# IMU.net
KiCad netlist of a schematic drawn in Altium Designer
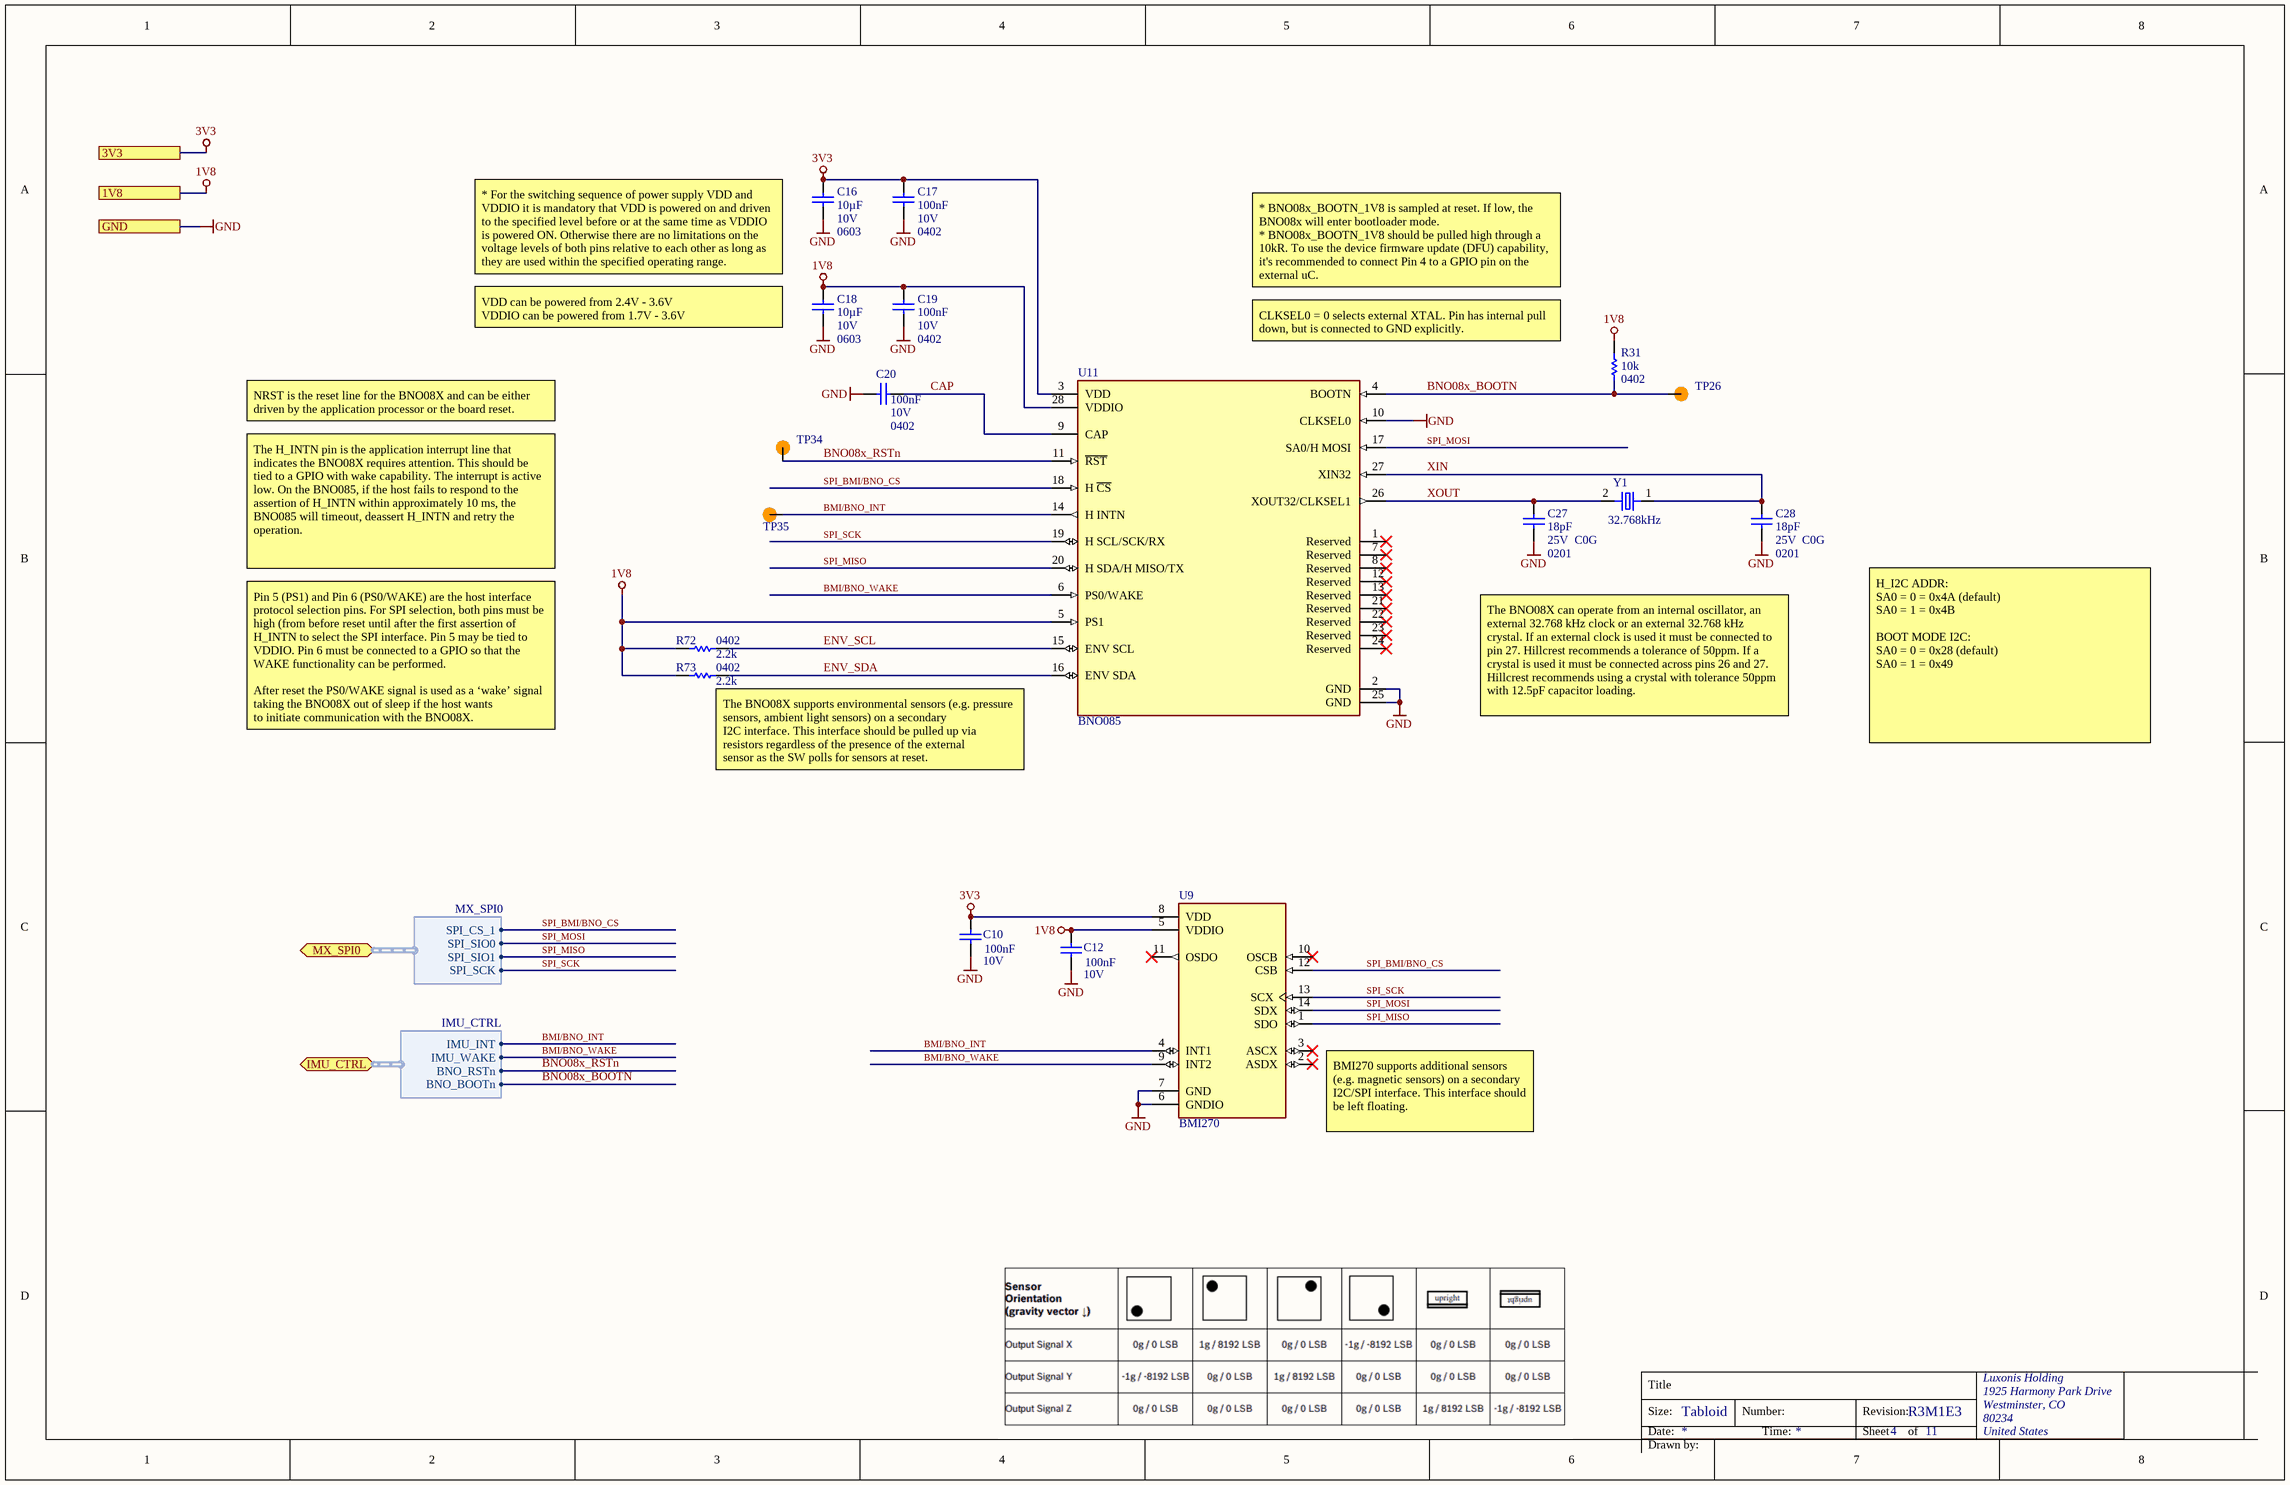
[diagram p0: IMU.SchDoc]

(export (version "E")
  (design (tool "Eeschema 10.0.6"))
  (components
    (comp (ref "C10")
      (value "100nF")
      (footprint "CAPC0402(1005)70_L")
      (description "CAP CER 0.1UF 10V X7R 0402 5%")
      (fields
        (field (name "TOLERANCE") "5%")
        (field (name "VOLTAGE RATING") "10V")
        (field (name "Comment") "GRM155R71A104JA01D")
      )
      (libsource (lib "Luxonis LLC") (part "GRM188R61C475KAAJD"))
    )
    (comp (ref "C12")
      (value "100nF")
      (footprint "CAPC0402(1005)70_L")
      (description "CAP CER 0.1UF 10V X7R 0402 5%")
      (fields
        (field (name "TOLERANCE") "5%")
        (field (name "VOLTAGE RATING") "10V")
        (field (name "Comment") "GRM155R71A104JA01D")
      )
      (libsource (lib "Luxonis LLC") (part "GRM188R61C475KAAJD"))
    )
    (comp (ref "C16")
      (value "10µF")
      (footprint "CAPC0603(1608)100_L")
      (description "CAP CER 10UF 10V X5R 0603 20%")
      (fields
        (field (name "CASE/PACKAGE") "0603")
        (field (name "TOLERANCE") "20%")
        (field (name "VOLTAGE RATING") "10V")
        (field (name "Comment") "GRM188R61A106ME69D")
      )
      (libsource (lib "Luxonis LLC") (part "LLL153C70G474ME17E"))
    )
    (comp (ref "C17")
      (value "100nF")
      (footprint "CAPC0402(1005)70_N")
      (description "CAP CER 0.1UF 10V X7R 0402 5%")
      (fields
        (field (name "CASE/PACKAGE") "0402")
        (field (name "TOLERANCE") "5%")
        (field (name "VOLTAGE RATING") "10V")
        (field (name "Comment") "GRM155R71A104JA01D")
      )
      (libsource (lib "Luxonis LLC") (part "GRM188R61C475KAAJD"))
    )
    (comp (ref "C18")
      (value "10µF")
      (footprint "CAPC0603(1608)100_L")
      (description "CAP CER 10UF 10V X5R 0603 20%")
      (fields
        (field (name "CASE/PACKAGE") "0603")
        (field (name "TOLERANCE") "20%")
        (field (name "VOLTAGE RATING") "10V")
        (field (name "Comment") "GRM188R61A106ME69D")
      )
      (libsource (lib "Luxonis LLC") (part "LLL153C70G474ME17E"))
    )
    (comp (ref "C19")
      (value "100nF")
      (footprint "CAPC0402(1005)70_N")
      (description "CAP CER 0.1UF 10V X7R 0402 5%")
      (fields
        (field (name "CASE/PACKAGE") "0402")
        (field (name "TOLERANCE") "5%")
        (field (name "VOLTAGE RATING") "10V")
        (field (name "Comment") "GRM155R71A104JA01D")
      )
      (libsource (lib "Luxonis LLC") (part "GRM188R61C475KAAJD"))
    )
    (comp (ref "C20")
      (value "100nF")
      (footprint "CAPC0402(1005)70_N")
      (description "CAP CER 0.1UF 10V X7R 0402 5%")
      (fields
        (field (name "CASE/PACKAGE") "0402")
        (field (name "TOLERANCE") "5%")
        (field (name "VOLTAGE RATING") "10V")
        (field (name "Comment") "GRM155R71A104JA01D")
      )
      (libsource (lib "Luxonis LLC") (part "GRM188R61C475KAAJD"))
    )
    (comp (ref "C27")
      (value "18pF")
      (footprint "CAPC0201(0603)33_L")
      (description "CAP CER 18PF 25V C0G 0201 10%")
      (fields
        (field (name "CASE/PACKAGE") "0201")
        (field (name "TOLERANCE") "1%")
        (field (name "VOLTAGE RATING") "25V")
        (field (name "DIELECTRIC") "C0G")
        (field (name "Comment") "GRM0335C1E180FA01D")
      )
      (libsource (lib "Luxonis LLC") (part "LLL153C70G474ME17E"))
    )
    (comp (ref "C28")
      (value "18pF")
      (footprint "CAPC0201(0603)33_L")
      (description "CAP CER 18PF 25V C0G 0201 10%")
      (fields
        (field (name "CASE/PACKAGE") "0201")
        (field (name "TOLERANCE") "1%")
        (field (name "VOLTAGE RATING") "25V")
        (field (name "DIELECTRIC") "C0G")
        (field (name "Comment") "GRM0335C1E180FA01D")
      )
      (libsource (lib "Luxonis LLC") (part "LLL153C70G474ME17E"))
    )
    (comp (ref "R31")
      (value "10k")
      (footprint "RESC0402(1005)_L")
      (description "RES SMD 10K OHM 1% 1/16W 0402")
      (fields
        (field (name "CASE/PACKAGE") "0402")
        (field (name "TOLERANCE") "1%")
        (field (name "Comment") "RC0402FR-1310KL")
      )
      (libsource (lib "Luxonis LLC") (part "RC0402FR-0722RL_1"))
    )
    (comp (ref "R72")
      (value "2.2k")
      (footprint "RESC0402(1005)_L")
      (description "RES SMD 2.2K OHM 1% 1/16W 0402")
      (fields
        (field (name "CASE/PACKAGE") "0402")
        (field (name "TOLERANCE") "1%")
        (field (name "Comment") "RC0402FR-072K2L")
      )
      (libsource (lib "Luxonis LLC") (part "Default resistor symbol"))
    )
    (comp (ref "R73")
      (value "2.2k")
      (footprint "RESC0402(1005)_L")
      (description "RES SMD 2.2K OHM 1% 1/16W 0402")
      (fields
        (field (name "CASE/PACKAGE") "0402")
        (field (name "TOLERANCE") "1%")
        (field (name "Comment") "RC0402FR-072K2L")
      )
      (libsource (lib "Luxonis LLC") (part "Default resistor symbol"))
    )
    (comp (ref "TP26")
      (value "TEST_POINT")
      (footprint "TP100_200_NS")
      (libsource (lib "Luxonis LLC") (part "TEST_POINT"))
    )
    (comp (ref "TP34")
      (value "TEST_POINT")
      (footprint "TP100_200_NS")
      (libsource (lib "Luxonis LLC") (part "TEST_POINT"))
    )
    (comp (ref "TP35")
      (value "TEST_POINT")
      (footprint "TP100_200_NS")
      (libsource (lib "Luxonis LLC") (part "TEST_POINT"))
    )
    (comp (ref "U9")
      (value "BMI270")
      (footprint "XDCR_BMI270")
      (description "Accelerometer, Gyroscope, 6 Axis Sensor IÂ²C, SPI Output")
      (libsource (lib "Luxonis LLC") (part "BMI270"))
    )
    (comp (ref "U11")
      (value "BNO085")
      (footprint "BNO085")
      (description "IMU ACCEL/GYRO/MAG I2C 32BIT")
      (libsource (lib "Luxonis LLC") (part "BNO085"))
    )
    (comp (ref "Y1")
      (value "ABS06-127-32.768KHZ-T")
      (footprint "ABS06-127-32.768KHZ-T")
      (description "CRYSTAL 32.768kHz ±20ppm Crystal 12.5pF 90 kOhms 2-SMD, No Lead")
      (fields (field (name "FREQUENCY") "32.768kHz") (field (name "TOLERANCE") "20ppm"))
      (libsource (lib "Luxonis LLC") (part "ABS06-127-32.768KHZ-T"))
    )
  )
  (nets
    (net (code "3") (name "/BMI{slash}BNO_INT") (class "Default")
      (node (ref "TP35") (pin "1") (pintype "passive"))
      (node (ref "U11") (pin "14") (pinfunction "H_INTN_14") (pintype "output"))
      (node (ref "U9") (pin "4") (pinfunction "INT1_4") (pintype "bidirectional"))
    )
    (net (code "4") (name "/BMI{slash}BNO_WAKE") (class "Default")
      (node (ref "U11") (pin "6") (pinfunction "PS0/WAKE_6") (pintype "input"))
      (node (ref "U9") (pin "9") (pinfunction "INT2_9") (pintype "bidirectional"))
    )
    (net (code "5") (name "/BNO08x_BOOTN") (class "Default")
      (node (ref "R31") (pin "1") (pinfunction "1_1") (pintype "passive"))
      (node (ref "TP26") (pin "1") (pintype "passive"))
      (node (ref "U11") (pin "4") (pinfunction "BOOTN_4") (pintype "input"))
    )
    (net (code "6") (name "/BNO08x_RSTn") (class "Default")
      (node (ref "TP34") (pin "1") (pintype "passive"))
      (node (ref "U11") (pin "11") (pinfunction "~{RST}_11") (pintype "input"))
    )
    (net (code "7") (name "/CAP") (class "Default")
      (node (ref "C20") (pin "1") (pinfunction "1_1") (pintype "passive"))
      (node (ref "U11") (pin "9") (pinfunction "CAP_9") (pintype "passive"))
    )
    (net (code "8") (name "/ENV_SCL") (class "Default")
      (node (ref "R72") (pin "2") (pinfunction "2_2") (pintype "passive"))
      (node (ref "U11") (pin "15") (pinfunction "ENV_SCL_15") (pintype "bidirectional"))
    )
    (net (code "9") (name "/ENV_SDA") (class "Default")
      (node (ref "R73") (pin "2") (pinfunction "2_2") (pintype "passive"))
      (node (ref "U11") (pin "16") (pinfunction "ENV_SDA_16") (pintype "bidirectional"))
    )
    (net (code "10") (name "/SPI_BMI{slash}BNO_CS") (class "Default")
      (node (ref "U11") (pin "18") (pinfunction "H_~{CS}_18") (pintype "input"))
      (node (ref "U9") (pin "12") (pinfunction "CSB_12") (pintype "input"))
    )
    (net (code "11") (name "/SPI_MISO") (class "Default")
      (node (ref "U11") (pin "20") (pinfunction "H_SDA/H_MISO/TX_20") (pintype "bidirectional"))
      (node (ref "U9") (pin "1") (pinfunction "SDO_1") (pintype "bidirectional"))
    )
    (net (code "12") (name "/SPI_MOSI") (class "Default")
      (node (ref "U11") (pin "17") (pinfunction "SA0/H_MOSI_17") (pintype "input"))
      (node (ref "U9") (pin "14") (pinfunction "SDX_14") (pintype "bidirectional"))
    )
    (net (code "13") (name "/SPI_SCK") (class "Default")
      (node (ref "U11") (pin "19") (pinfunction "H_SCL/SCK/RX_19") (pintype "bidirectional"))
      (node (ref "U9") (pin "13") (pinfunction "SCX_13") (pintype "input"))
    )
    (net (code "14") (name "/XIN") (class "Default")
      (node (ref "C28") (pin "2") (pinfunction "2_2") (pintype "passive"))
      (node (ref "U11") (pin "27") (pinfunction "XIN32_27") (pintype "input"))
      (node (ref "Y1") (pin "1") (pinfunction "1_1") (pintype "passive"))
    )
    (net (code "15") (name "/XOUT") (class "Default")
      (node (ref "C27") (pin "2") (pinfunction "2_2") (pintype "passive"))
      (node (ref "U11") (pin "26") (pinfunction "XOUT32/CLKSEL1_26") (pintype "output"))
      (node (ref "Y1") (pin "2") (pinfunction "2_2") (pintype "passive"))
    )
    (net (code "18") (name "1V8") (class "Default")
      (node (ref "C12") (pin "2") (pinfunction "2_2") (pintype "passive"))
      (node (ref "C18") (pin "2") (pinfunction "2_2") (pintype "passive"))
      (node (ref "C19") (pin "2") (pinfunction "2_2") (pintype "passive"))
      (node (ref "R31") (pin "2") (pinfunction "2_2") (pintype "passive"))
      (node (ref "R72") (pin "1") (pinfunction "1_1") (pintype "passive"))
      (node (ref "R73") (pin "1") (pinfunction "1_1") (pintype "passive"))
      (node (ref "U11") (pin "28") (pinfunction "VDDIO_28") (pintype "power_in"))
      (node (ref "U11") (pin "5") (pinfunction "PS1_5") (pintype "input"))
      (node (ref "U9") (pin "5") (pinfunction "VDDIO_5") (pintype "power_in"))
    )
    (net (code "19") (name "3V3") (class "Default")
      (node (ref "C10") (pin "2") (pinfunction "2_2") (pintype "passive"))
      (node (ref "C16") (pin "2") (pinfunction "2_2") (pintype "passive"))
      (node (ref "C17") (pin "2") (pinfunction "2_2") (pintype "passive"))
      (node (ref "U11") (pin "3") (pinfunction "VDD_3") (pintype "power_in"))
      (node (ref "U9") (pin "8") (pinfunction "VDD_8") (pintype "power_in"))
    )
    (net (code "20") (name "GND") (class "Default")
      (node (ref "C10") (pin "1") (pinfunction "1_1") (pintype "passive"))
      (node (ref "C12") (pin "1") (pinfunction "1_1") (pintype "passive"))
      (node (ref "C16") (pin "1") (pinfunction "1_1") (pintype "passive"))
      (node (ref "C17") (pin "1") (pinfunction "1_1") (pintype "passive"))
      (node (ref "C18") (pin "1") (pinfunction "1_1") (pintype "passive"))
      (node (ref "C19") (pin "1") (pinfunction "1_1") (pintype "passive"))
      (node (ref "C20") (pin "2") (pinfunction "2_2") (pintype "passive"))
      (node (ref "C27") (pin "1") (pinfunction "1_1") (pintype "passive"))
      (node (ref "C28") (pin "1") (pinfunction "1_1") (pintype "passive"))
      (node (ref "U11") (pin "10") (pinfunction "CLKSEL0_10") (pintype "input"))
      (node (ref "U11") (pin "2") (pinfunction "GND_2") (pintype "power_in"))
      (node (ref "U11") (pin "25") (pinfunction "GND_25") (pintype "power_in"))
      (node (ref "U9") (pin "6") (pinfunction "GNDIO_6") (pintype "power_in"))
      (node (ref "U9") (pin "7") (pinfunction "GND_7") (pintype "power_in"))
    )
    (net (code "21") (name "unconnected-(U9-ASCX-Pad3)") (class "Default")
      (node (ref "U9") (pin "3") (pinfunction "ASCX_3") (pintype "bidirectional+no_connect"))
    )
    (net (code "22") (name "unconnected-(U9-ASDX-Pad2)") (class "Default")
      (node (ref "U9") (pin "2") (pinfunction "ASDX_2") (pintype "bidirectional+no_connect"))
    )
    (net (code "23") (name "unconnected-(U9-OSCB-Pad10)") (class "Default")
      (node (ref "U9") (pin "10") (pinfunction "OSCB_10") (pintype "input+no_connect"))
    )
    (net (code "24") (name "unconnected-(U9-OSDO-Pad11)") (class "Default")
      (node (ref "U9") (pin "11") (pinfunction "OSDO_11") (pintype "output+no_connect"))
    )
    (net (code "25") (name "unconnected-(U11-Reserved-Pad1)") (class "Default")
      (node (ref "U11") (pin "1") (pinfunction "Reserved_1") (pintype "passive+no_connect"))
    )
    (net (code "26") (name "unconnected-(U11-Reserved-Pad7)") (class "Default")
      (node (ref "U11") (pin "7") (pinfunction "Reserved_7") (pintype "passive+no_connect"))
    )
    (net (code "27") (name "unconnected-(U11-Reserved-Pad8)") (class "Default")
      (node (ref "U11") (pin "8") (pinfunction "Reserved_8") (pintype "passive+no_connect"))
    )
    (net (code "28") (name "unconnected-(U11-Reserved-Pad12)") (class "Default")
      (node (ref "U11") (pin "12") (pinfunction "Reserved_12") (pintype "passive+no_connect"))
    )
    (net (code "29") (name "unconnected-(U11-Reserved-Pad13)") (class "Default")
      (node (ref "U11") (pin "13") (pinfunction "Reserved_13") (pintype "passive+no_connect"))
    )
    (net (code "30") (name "unconnected-(U11-Reserved-Pad21)") (class "Default")
      (node (ref "U11") (pin "21") (pinfunction "Reserved_21") (pintype "passive+no_connect"))
    )
    (net (code "31") (name "unconnected-(U11-Reserved-Pad22)") (class "Default")
      (node (ref "U11") (pin "22") (pinfunction "Reserved_22") (pintype "passive+no_connect"))
    )
    (net (code "32") (name "unconnected-(U11-Reserved-Pad23)") (class "Default")
      (node (ref "U11") (pin "23") (pinfunction "Reserved_23") (pintype "passive+no_connect"))
    )
    (net (code "33") (name "unconnected-(U11-Reserved-Pad24)") (class "Default")
      (node (ref "U11") (pin "24") (pinfunction "Reserved_24") (pintype "passive+no_connect"))
    )
  )
)
